# SCH.net
KiCad netlist of a schematic drawn in Altium Designer
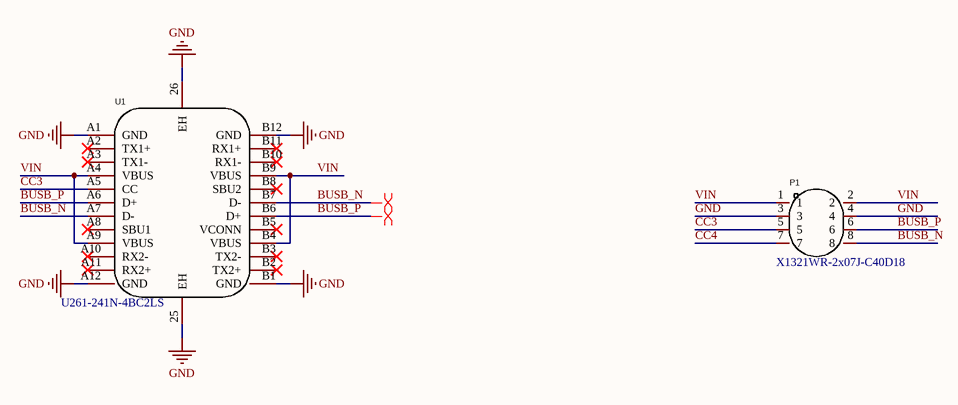
[diagram p0: SCH.SchDoc]

(export (version "E")
  (design (tool "Eeschema 10.0.6"))
  (components
    (comp (ref "P1")
      (value "X1321WR-2x07J-C40D18")
      (footprint "HDR-TH_8P-P1.27-L")
      (description "双排弯针2*4P")
      (fields (field (name "MANUFACTURER") "XKB Connectivity(中国星坤)"))
      (libsource (lib "DHO800_Battery_Pack_LED_V1.0") (part "双排插针"))
    )
    (comp (ref "U1")
      (value "U261-241N-4BC2LS")
      (footprint "USB-C-SMD_XKB_U261-241N-4BC2LS")
      (description "USB C公头")
      (fields (field (name "MANUFACTURER") "XKB Connectivity(中国星坤)"))
      (libsource (lib "DHO800_Battery_Pack_IP5389_V1.0_1") (part "U261-241N-4BC2LS"))
    )
  )
  (nets
    (net (code "1") (name "/BUSB_N") (class "Default")
      (node (ref "P1") (pin "8") (pinfunction "8_8") (pintype "passive"))
      (node (ref "U1") (pin "A7") (pinfunction "D-_A7") (pintype "passive"))
      (node (ref "U1") (pin "B7") (pinfunction "D-_B7") (pintype "passive"))
    )
    (net (code "2") (name "/BUSB_P") (class "Default")
      (node (ref "P1") (pin "6") (pinfunction "6_6") (pintype "passive"))
      (node (ref "U1") (pin "A6") (pinfunction "D+_A6") (pintype "passive"))
      (node (ref "U1") (pin "B6") (pinfunction "D+_B6") (pintype "passive"))
    )
    (net (code "3") (name "/CC3") (class "Default")
      (node (ref "P1") (pin "5") (pinfunction "5_5") (pintype "passive"))
      (node (ref "U1") (pin "A5") (pinfunction "CC_A5") (pintype "passive"))
    )
    (net (code "4") (name "/CC4") (class "Default")
      (node (ref "P1") (pin "7") (pinfunction "7_7") (pintype "passive"))
    )
    (net (code "5") (name "/VIN") (class "Default")
      (node (ref "P1") (pin "1") (pinfunction "1_1") (pintype "passive"))
      (node (ref "P1") (pin "2") (pinfunction "2_2") (pintype "passive"))
      (node (ref "U1") (pin "A4") (pinfunction "VBUS_A4") (pintype "passive"))
      (node (ref "U1") (pin "A9") (pinfunction "VBUS_A9") (pintype "passive"))
      (node (ref "U1") (pin "B4") (pinfunction "VBUS_B4") (pintype "passive"))
      (node (ref "U1") (pin "B9") (pinfunction "VBUS_B9") (pintype "passive"))
    )
    (net (code "6") (name "GND") (class "Default")
      (node (ref "P1") (pin "3") (pinfunction "3_3") (pintype "passive"))
      (node (ref "P1") (pin "4") (pinfunction "4_4") (pintype "passive"))
      (node (ref "U1") (pin "25") (pinfunction "EH_25") (pintype "passive"))
      (node (ref "U1") (pin "26") (pinfunction "EH_26") (pintype "passive"))
      (node (ref "U1") (pin "A1") (pinfunction "GND_A1") (pintype "passive"))
      (node (ref "U1") (pin "A12") (pinfunction "GND_A12") (pintype "passive"))
      (node (ref "U1") (pin "B1") (pinfunction "GND_B1") (pintype "passive"))
      (node (ref "U1") (pin "B12") (pinfunction "GND_B12") (pintype "passive"))
    )
    (net (code "7") (name "unconnected-(U1-RX1+-PadB11)") (class "Default")
      (node (ref "U1") (pin "B11") (pinfunction "RX1+_B11") (pintype "passive+no_connect"))
    )
    (net (code "8") (name "unconnected-(U1-RX1--PadB10)") (class "Default")
      (node (ref "U1") (pin "B10") (pinfunction "RX1-_B10") (pintype "passive+no_connect"))
    )
    (net (code "9") (name "unconnected-(U1-RX2+-PadA11)") (class "Default")
      (node (ref "U1") (pin "A11") (pinfunction "RX2+_A11") (pintype "passive+no_connect"))
    )
    (net (code "10") (name "unconnected-(U1-RX2--PadA10)") (class "Default")
      (node (ref "U1") (pin "A10") (pinfunction "RX2-_A10") (pintype "passive+no_connect"))
    )
    (net (code "11") (name "unconnected-(U1-SBU1-PadA8)") (class "Default")
      (node (ref "U1") (pin "A8") (pinfunction "SBU1_A8") (pintype "passive+no_connect"))
    )
    (net (code "12") (name "unconnected-(U1-SBU2-PadB8)") (class "Default")
      (node (ref "U1") (pin "B8") (pinfunction "SBU2_B8") (pintype "passive+no_connect"))
    )
    (net (code "13") (name "unconnected-(U1-TX1+-PadA2)") (class "Default")
      (node (ref "U1") (pin "A2") (pinfunction "TX1+_A2") (pintype "passive+no_connect"))
    )
    (net (code "14") (name "unconnected-(U1-TX1--PadA3)") (class "Default")
      (node (ref "U1") (pin "A3") (pinfunction "TX1-_A3") (pintype "passive+no_connect"))
    )
    (net (code "15") (name "unconnected-(U1-TX2+-PadB2)") (class "Default")
      (node (ref "U1") (pin "B2") (pinfunction "TX2+_B2") (pintype "passive+no_connect"))
    )
    (net (code "16") (name "unconnected-(U1-TX2--PadB3)") (class "Default")
      (node (ref "U1") (pin "B3") (pinfunction "TX2-_B3") (pintype "passive+no_connect"))
    )
    (net (code "17") (name "unconnected-(U1-VCONN-PadB5)") (class "Default")
      (node (ref "U1") (pin "B5") (pinfunction "VCONN_B5") (pintype "passive+no_connect"))
    )
  )
)
